# 05_MIMXRT1170_PART1.net
KiCad netlist of a schematic drawn in Altium Designer
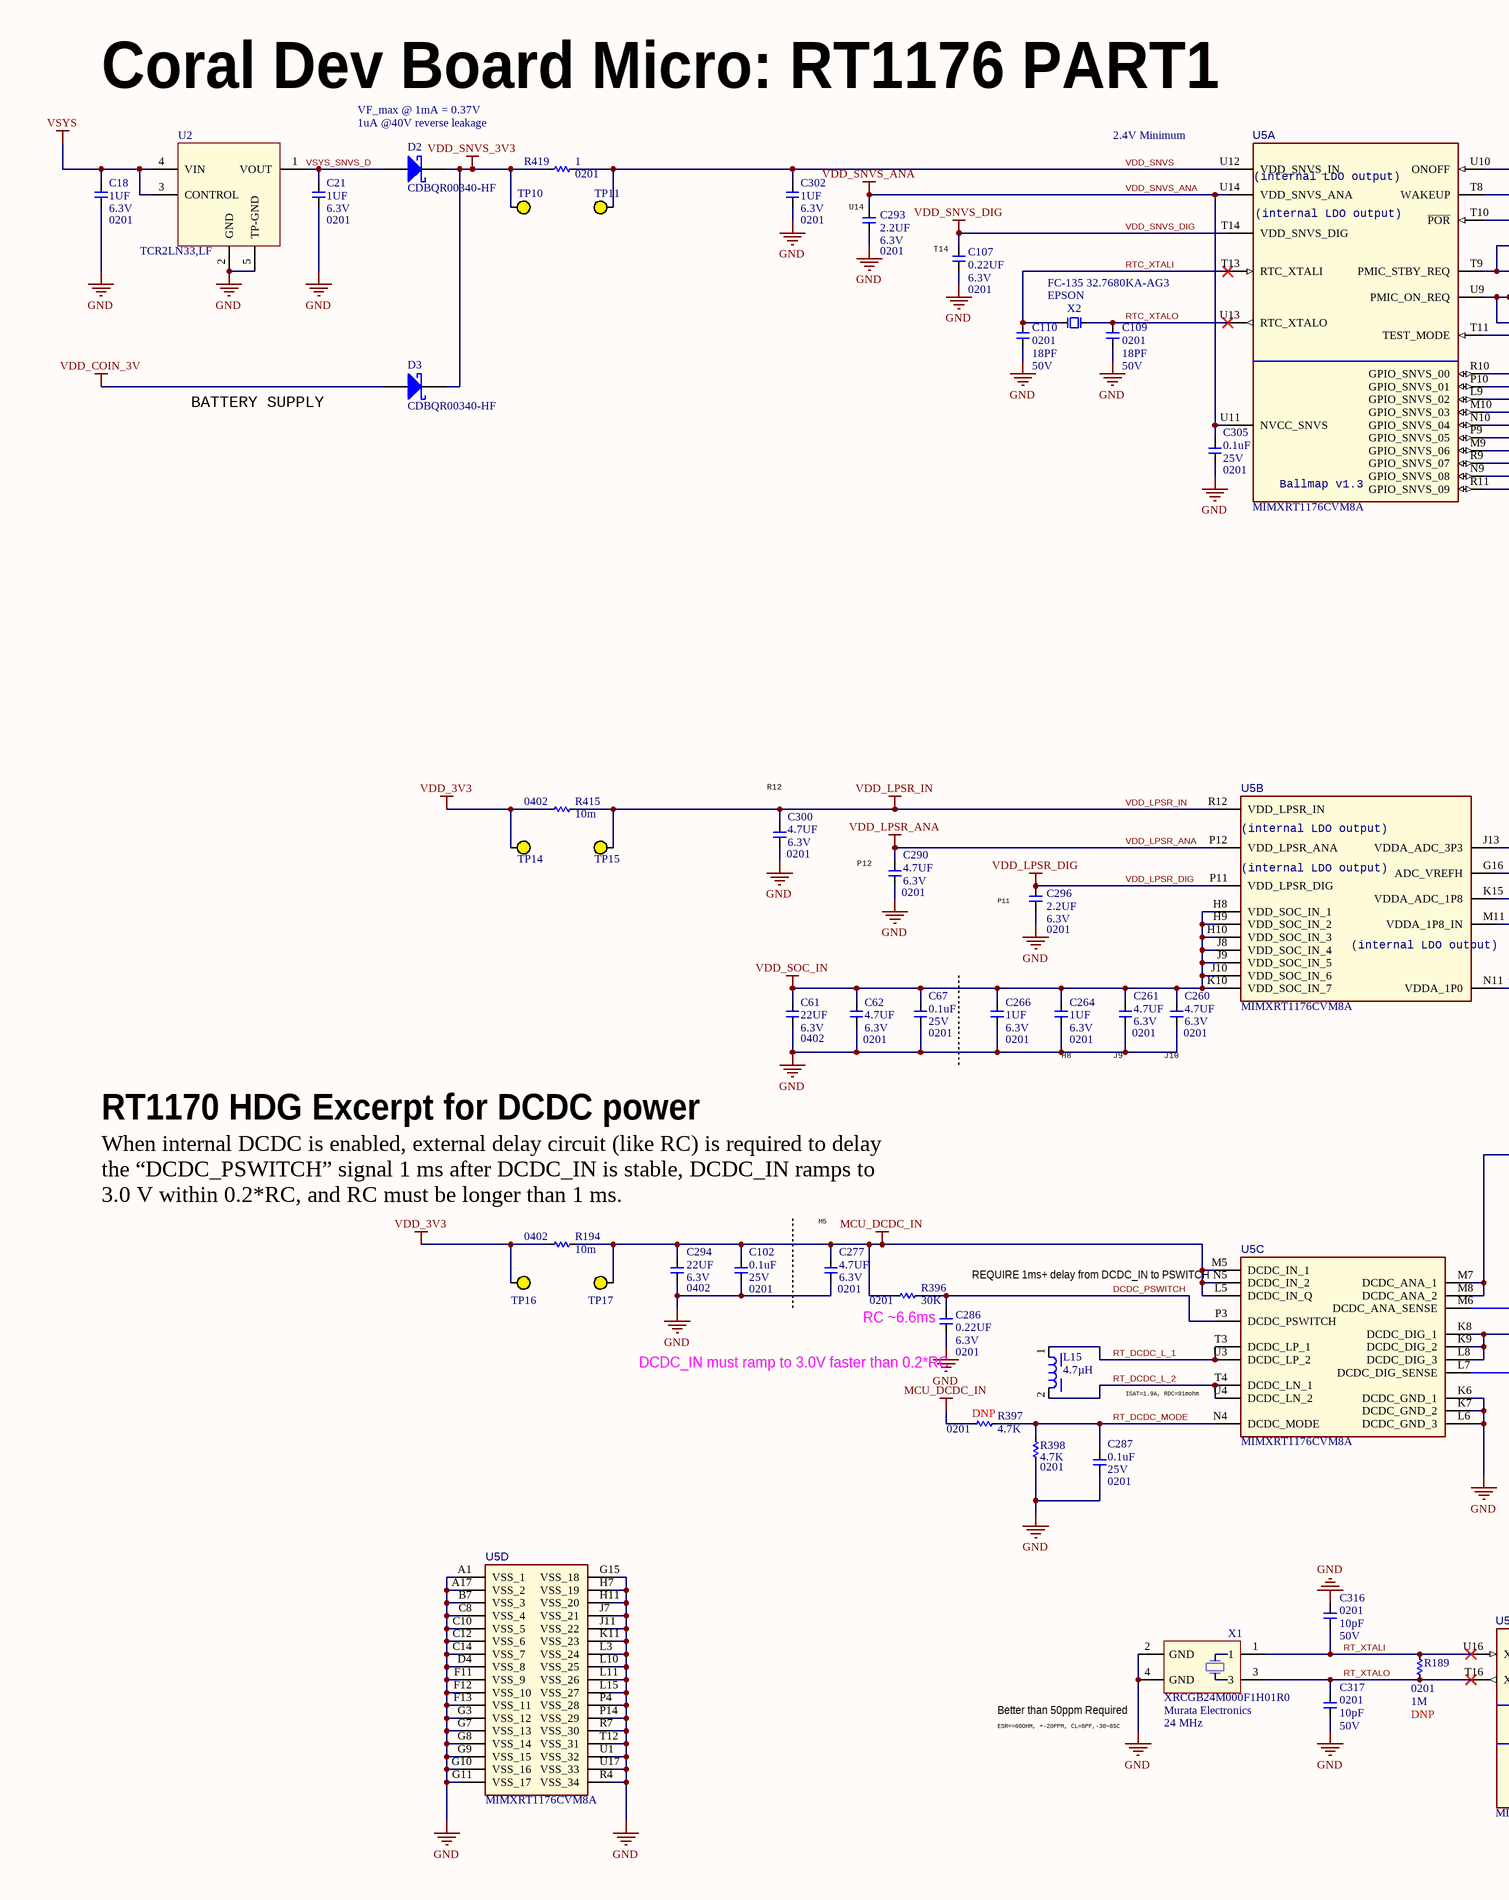
[diagram p0: 05 MIMXRT1170 PART1.SchDoc, left]
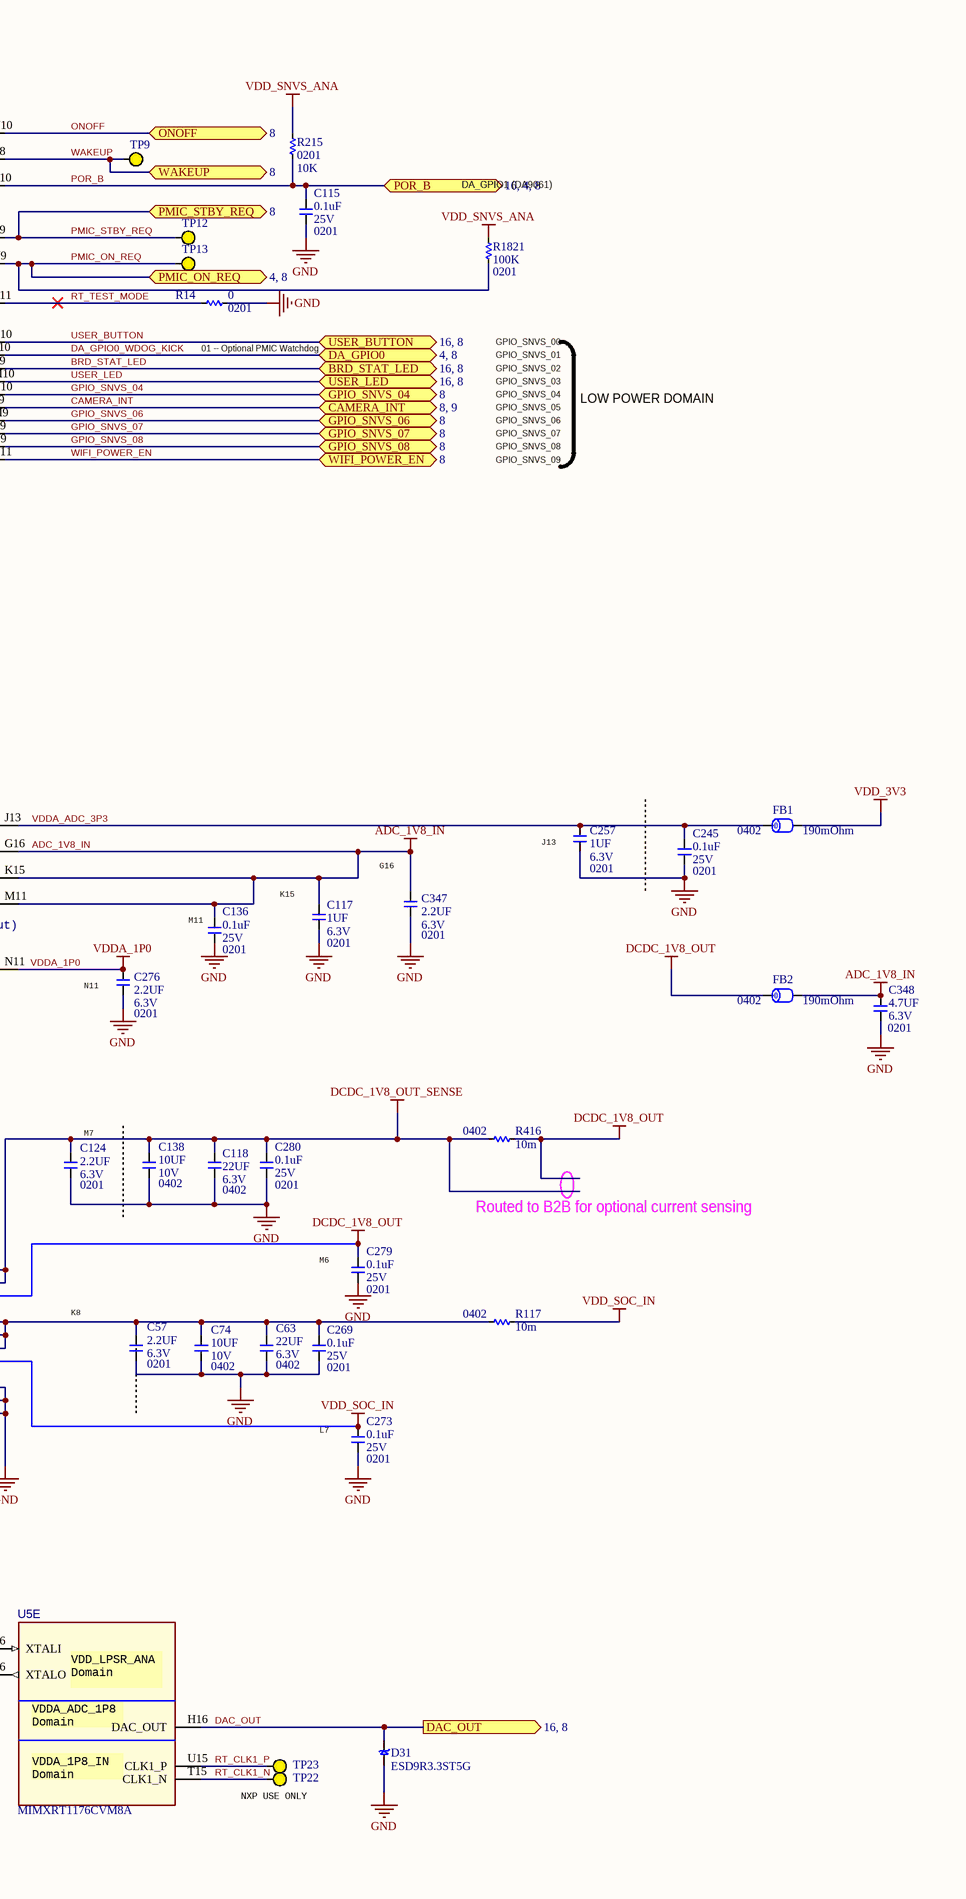
[diagram p1: 05 MIMXRT1170 PART1.SchDoc, right]

(export (version "E")
  (design (tool "Eeschema 10.0.6"))
  (components
    (comp (ref "C18")
      (value "1UF")
      (footprint "C0201_H0.39MM")
      (description "CAP, CER, X6S, 1uF, 20%, 6.3V, 0201, 0.39mm")
      (fields
        (field (name "MFG") "MURATA")
        (field (name "PACKAGE") "0201")
        (field (name "VOLTAGE") "6.3V")
        (field (name "TOLERANCE") "20%")
      )
      (libsource (lib "AltiumReleaseLibDB") (part "__Template_Cap"))
    )
    (comp (ref "C21")
      (value "1UF")
      (footprint "C0201_H0.39MM")
      (description "CAP, CER, X6S, 1uF, 20%, 6.3V, 0201, 0.39mm")
      (fields
        (field (name "MFG") "MURATA")
        (field (name "PACKAGE") "0201")
        (field (name "VOLTAGE") "6.3V")
        (field (name "TOLERANCE") "20%")
      )
      (libsource (lib "AltiumReleaseLibDB") (part "__Template_Cap"))
    )
    (comp (ref "C57")
      (value "2.2UF")
      (footprint "C0201_H0.39MM")
      (description "CAP, CER, X5R, 2.2uF, 20%, 6.3V, 0201, 0.39mm")
      (fields
        (field (name "MFG") "YAGEO")
        (field (name "PACKAGE") "0201")
        (field (name "VOLTAGE") "6.3V")
        (field (name "TOLERANCE") "20%")
      )
      (libsource (lib "AltiumReleaseLibDB") (part "__Template_Cap"))
    )
    (comp (ref "C61")
      (value "22UF")
      (footprint "C0402")
      (description "CAP, CER, X5R, 22uF, 20%, 6.3V, 0402")
      (fields
        (field (name "MFG") "AVX")
        (field (name "PACKAGE") "0402")
        (field (name "VOLTAGE") "6.3V")
        (field (name "TOLERANCE") "20%")
      )
      (libsource (lib "AltiumReleaseLibDB") (part "__Template_Cap"))
    )
    (comp (ref "C62")
      (value "4.7UF")
      (footprint "C0201Y")
      (description "CAP, CER, X5R, 4.7uF, 20%, 6.3V, 0201")
      (fields
        (field (name "MFG") "MURATA")
        (field (name "PACKAGE") "0201")
        (field (name "VOLTAGE") "6.3V")
        (field (name "TOLERANCE") "20%")
      )
      (libsource (lib "AltiumReleaseLibDB") (part "__Template_Cap"))
    )
    (comp (ref "C63")
      (value "22UF")
      (footprint "C0402")
      (description "CAP, CER, X5R, 22uF, 20%, 6.3V, 0402")
      (fields
        (field (name "MFG") "AVX")
        (field (name "PACKAGE") "0402")
        (field (name "VOLTAGE") "6.3V")
        (field (name "TOLERANCE") "20%")
      )
      (libsource (lib "AltiumReleaseLibDB") (part "__Template_Cap"))
    )
    (comp (ref "C67")
      (value "0.1uF")
      (footprint "C0201Y")
      (description "CAP, CER, X5R, 0.1uF, 25V, 20%, 0201, 0.33mm T")
      (fields
        (field (name "MFG") "MURATA")
        (field (name "PACKAGE") "0201")
        (field (name "VOLTAGE") "25V")
        (field (name "TOLERANCE") "20%")
      )
      (libsource (lib "AltiumReleaseLibDB") (part "__Template_Cap"))
    )
    (comp (ref "C74")
      (value "10UF")
      (footprint "C0402")
      (description "CAP, CER, X5R, 10uF, 10V, 20%, 0402, 0.7mm T")
      (fields
        (field (name "MFG") "SAMSUNG")
        (field (name "PACKAGE") "0402")
        (field (name "VOLTAGE") "10V")
        (field (name "TOLERANCE") "20%")
      )
      (libsource (lib "AltiumReleaseLibDB") (part "__Template_Cap"))
    )
    (comp (ref "C102")
      (value "0.1uF")
      (footprint "C0201Y")
      (description "CAP, CER, X5R, 0.1uF, 25V, 20%, 0201, 0.33mm T")
      (fields
        (field (name "MFG") "MURATA")
        (field (name "PACKAGE") "0201")
        (field (name "VOLTAGE") "25V")
        (field (name "TOLERANCE") "20%")
      )
      (libsource (lib "AltiumReleaseLibDB") (part "__Template_Cap"))
    )
    (comp (ref "C107")
      (value "0.22UF")
      (footprint "C0201")
      (description "CAP, CER, X5R, 0.22uF, 6.3V, 10%, 0201, 0.33mm T")
      (fields
        (field (name "MFG") "TDK")
        (field (name "PACKAGE") "0201")
        (field (name "VOLTAGE") "6.3V")
        (field (name "TOLERANCE") "10%")
      )
      (libsource (lib "AltiumReleaseLibDB") (part "__Template_Cap"))
    )
    (comp (ref "C109")
      (value "18PF")
      (footprint "C0201Y")
      (description "CAP, CER, C0G, 18pF, 50V, 2%, 0201, 0.33mm T")
      (fields
        (field (name "MFG") "MURATA")
        (field (name "PACKAGE") "0201")
        (field (name "VOLTAGE") "50V")
        (field (name "TOLERANCE") "2%")
      )
      (libsource (lib "AltiumReleaseLibDB") (part "__Template_Cap"))
    )
    (comp (ref "C110")
      (value "18PF")
      (footprint "C0201Y")
      (description "CAP, CER, C0G, 18pF, 50V, 2%, 0201, 0.33mm T")
      (fields
        (field (name "MFG") "MURATA")
        (field (name "PACKAGE") "0201")
        (field (name "VOLTAGE") "50V")
        (field (name "TOLERANCE") "2%")
      )
      (libsource (lib "AltiumReleaseLibDB") (part "__Template_Cap"))
    )
    (comp (ref "C115")
      (value "0.1uF")
      (footprint "C0201Y")
      (description "CAP, CER, X5R, 0.1uF, 25V, 20%, 0201, 0.33mm T")
      (fields
        (field (name "MFG") "MURATA")
        (field (name "PACKAGE") "0201")
        (field (name "VOLTAGE") "25V")
        (field (name "TOLERANCE") "20%")
      )
      (libsource (lib "AltiumReleaseLibDB") (part "__Template_Cap"))
    )
    (comp (ref "C117")
      (value "1UF")
      (footprint "C0201_H0.39MM")
      (description "CAP, CER, X6S, 1uF, 20%, 6.3V, 0201, 0.39mm")
      (fields
        (field (name "MFG") "MURATA")
        (field (name "PACKAGE") "0201")
        (field (name "VOLTAGE") "6.3V")
        (field (name "TOLERANCE") "20%")
      )
      (libsource (lib "AltiumReleaseLibDB") (part "__Template_Cap"))
    )
    (comp (ref "C118")
      (value "22UF")
      (footprint "C0402")
      (description "CAP, CER, X5R, 22uF, 20%, 6.3V, 0402")
      (fields
        (field (name "MFG") "AVX")
        (field (name "PACKAGE") "0402")
        (field (name "VOLTAGE") "6.3V")
        (field (name "TOLERANCE") "20%")
      )
      (libsource (lib "AltiumReleaseLibDB") (part "__Template_Cap"))
    )
    (comp (ref "C124")
      (value "2.2UF")
      (footprint "C0201_H0.39MM")
      (description "CAP, CER, X5R, 2.2uF, 20%, 6.3V, 0201, 0.39mm")
      (fields
        (field (name "MFG") "YAGEO")
        (field (name "PACKAGE") "0201")
        (field (name "VOLTAGE") "6.3V")
        (field (name "TOLERANCE") "20%")
      )
      (libsource (lib "AltiumReleaseLibDB") (part "__Template_Cap"))
    )
    (comp (ref "C136")
      (value "0.1uF")
      (footprint "C0201Y")
      (description "CAP, CER, X5R, 0.1uF, 25V, 20%, 0201, 0.33mm T")
      (fields
        (field (name "MFG") "MURATA")
        (field (name "PACKAGE") "0201")
        (field (name "VOLTAGE") "25V")
        (field (name "TOLERANCE") "20%")
      )
      (libsource (lib "AltiumReleaseLibDB") (part "__Template_Cap"))
    )
    (comp (ref "C138")
      (value "10UF")
      (footprint "C0402")
      (description "CAP, CER, X5R, 10uF, 10V, 20%, 0402, 0.7mm T")
      (fields
        (field (name "MFG") "SAMSUNG")
        (field (name "PACKAGE") "0402")
        (field (name "VOLTAGE") "10V")
        (field (name "TOLERANCE") "20%")
      )
      (libsource (lib "AltiumReleaseLibDB") (part "__Template_Cap"))
    )
    (comp (ref "C245")
      (value "0.1uF")
      (footprint "C0201Y")
      (description "CAP, CER, X5R, 0.1uF, 25V, 20%, 0201, 0.33mm T")
      (fields
        (field (name "MFG") "MURATA")
        (field (name "PACKAGE") "0201")
        (field (name "VOLTAGE") "25V")
        (field (name "TOLERANCE") "20%")
      )
      (libsource (lib "AltiumReleaseLibDB") (part "__Template_Cap"))
    )
    (comp (ref "C257")
      (value "1UF")
      (footprint "C0201_H0.39MM")
      (description "CAP, CER, X6S, 1uF, 20%, 6.3V, 0201, 0.39mm")
      (fields
        (field (name "MFG") "MURATA")
        (field (name "PACKAGE") "0201")
        (field (name "VOLTAGE") "6.3V")
        (field (name "TOLERANCE") "20%")
      )
      (libsource (lib "AltiumReleaseLibDB") (part "__Template_Cap"))
    )
    (comp (ref "C260")
      (value "4.7UF")
      (footprint "C0201Y")
      (description "CAP, CER, X5R, 4.7uF, 20%, 6.3V, 0201")
      (fields
        (field (name "MFG") "MURATA")
        (field (name "PACKAGE") "0201")
        (field (name "VOLTAGE") "6.3V")
        (field (name "TOLERANCE") "20%")
      )
      (libsource (lib "AltiumReleaseLibDB") (part "__Template_Cap"))
    )
    (comp (ref "C261")
      (value "4.7UF")
      (footprint "C0201Y")
      (description "CAP, CER, X5R, 4.7uF, 20%, 6.3V, 0201")
      (fields
        (field (name "MFG") "MURATA")
        (field (name "PACKAGE") "0201")
        (field (name "VOLTAGE") "6.3V")
        (field (name "TOLERANCE") "20%")
      )
      (libsource (lib "AltiumReleaseLibDB") (part "__Template_Cap"))
    )
    (comp (ref "C264")
      (value "1UF")
      (footprint "C0201_H0.39MM")
      (description "CAP, CER, X6S, 1uF, 20%, 6.3V, 0201, 0.39mm")
      (fields
        (field (name "MFG") "MURATA")
        (field (name "PACKAGE") "0201")
        (field (name "VOLTAGE") "6.3V")
        (field (name "TOLERANCE") "20%")
      )
      (libsource (lib "AltiumReleaseLibDB") (part "__Template_Cap"))
    )
    (comp (ref "C266")
      (value "1UF")
      (footprint "C0201_H0.39MM")
      (description "CAP, CER, X6S, 1uF, 20%, 6.3V, 0201, 0.39mm")
      (fields
        (field (name "MFG") "MURATA")
        (field (name "PACKAGE") "0201")
        (field (name "VOLTAGE") "6.3V")
        (field (name "TOLERANCE") "20%")
      )
      (libsource (lib "AltiumReleaseLibDB") (part "__Template_Cap"))
    )
    (comp (ref "C269")
      (value "0.1uF")
      (footprint "C0201Y")
      (description "CAP, CER, X5R, 0.1uF, 25V, 20%, 0201, 0.33mm T")
      (fields
        (field (name "MFG") "MURATA")
        (field (name "PACKAGE") "0201")
        (field (name "VOLTAGE") "25V")
        (field (name "TOLERANCE") "20%")
      )
      (libsource (lib "AltiumReleaseLibDB") (part "__Template_Cap"))
    )
    (comp (ref "C273")
      (value "0.1uF")
      (footprint "C0201Y")
      (description "CAP, CER, X5R, 0.1uF, 25V, 20%, 0201, 0.33mm T")
      (fields
        (field (name "MFG") "MURATA")
        (field (name "PACKAGE") "0201")
        (field (name "VOLTAGE") "25V")
        (field (name "TOLERANCE") "20%")
      )
      (libsource (lib "AltiumReleaseLibDB") (part "__Template_Cap"))
    )
    (comp (ref "C276")
      (value "2.2UF")
      (footprint "C0201_H0.39MM")
      (description "CAP, CER, X5R, 2.2uF, 20%, 6.3V, 0201, 0.39mm")
      (fields
        (field (name "MFG") "YAGEO")
        (field (name "PACKAGE") "0201")
        (field (name "VOLTAGE") "6.3V")
        (field (name "TOLERANCE") "20%")
      )
      (libsource (lib "AltiumReleaseLibDB") (part "__Template_Cap"))
    )
    (comp (ref "C277")
      (value "4.7UF")
      (footprint "C0201Y")
      (description "CAP, CER, X5R, 4.7uF, 20%, 6.3V, 0201")
      (fields
        (field (name "MFG") "MURATA")
        (field (name "PACKAGE") "0201")
        (field (name "VOLTAGE") "6.3V")
        (field (name "TOLERANCE") "20%")
      )
      (libsource (lib "AltiumReleaseLibDB") (part "__Template_Cap"))
    )
    (comp (ref "C279")
      (value "0.1uF")
      (footprint "C0201Y")
      (description "CAP, CER, X5R, 0.1uF, 25V, 20%, 0201, 0.33mm T")
      (fields
        (field (name "MFG") "MURATA")
        (field (name "PACKAGE") "0201")
        (field (name "VOLTAGE") "25V")
        (field (name "TOLERANCE") "20%")
      )
      (libsource (lib "AltiumReleaseLibDB") (part "__Template_Cap"))
    )
    (comp (ref "C280")
      (value "0.1uF")
      (footprint "C0201Y")
      (description "CAP, CER, X5R, 0.1uF, 25V, 20%, 0201, 0.33mm T")
      (fields
        (field (name "MFG") "MURATA")
        (field (name "PACKAGE") "0201")
        (field (name "VOLTAGE") "25V")
        (field (name "TOLERANCE") "20%")
      )
      (libsource (lib "AltiumReleaseLibDB") (part "__Template_Cap"))
    )
    (comp (ref "C286")
      (value "0.22UF")
      (footprint "C0201")
      (description "CAP, CER, X5R, 0.22uF, 6.3V, 10%, 0201, 0.33mm T")
      (fields
        (field (name "MFG") "TDK")
        (field (name "PACKAGE") "0201")
        (field (name "VOLTAGE") "6.3V")
        (field (name "TOLERANCE") "10%")
      )
      (libsource (lib "AltiumReleaseLibDB") (part "__Template_Cap"))
    )
    (comp (ref "C287")
      (value "0.1uF")
      (footprint "C0201Y")
      (description "CAP, CER, X5R, 0.1uF, 25V, 20%, 0201, 0.33mm T")
      (fields
        (field (name "MFG") "MURATA")
        (field (name "PACKAGE") "0201")
        (field (name "VOLTAGE") "25V")
        (field (name "TOLERANCE") "20%")
      )
      (libsource (lib "AltiumReleaseLibDB") (part "__Template_Cap"))
    )
    (comp (ref "C290")
      (value "4.7UF")
      (footprint "C0201Y")
      (description "CAP, CER, X5R, 4.7uF, 20%, 6.3V, 0201")
      (fields
        (field (name "MFG") "MURATA")
        (field (name "PACKAGE") "0201")
        (field (name "VOLTAGE") "6.3V")
        (field (name "TOLERANCE") "20%")
      )
      (libsource (lib "AltiumReleaseLibDB") (part "__Template_Cap"))
    )
    (comp (ref "C293")
      (value "2.2UF")
      (footprint "C0201_H0.39MM")
      (description "CAP, CER, X5R, 2.2uF, 20%, 6.3V, 0201, 0.39mm")
      (fields
        (field (name "MFG") "YAGEO")
        (field (name "PACKAGE") "0201")
        (field (name "VOLTAGE") "6.3V")
        (field (name "TOLERANCE") "20%")
      )
      (libsource (lib "AltiumReleaseLibDB") (part "__Template_Cap"))
    )
    (comp (ref "C294")
      (value "22UF")
      (footprint "C0402")
      (description "CAP, CER, X5R, 22uF, 20%, 6.3V, 0402")
      (fields
        (field (name "MFG") "AVX")
        (field (name "PACKAGE") "0402")
        (field (name "VOLTAGE") "6.3V")
        (field (name "TOLERANCE") "20%")
      )
      (libsource (lib "AltiumReleaseLibDB") (part "__Template_Cap"))
    )
    (comp (ref "C296")
      (value "2.2UF")
      (footprint "C0201_H0.39MM")
      (description "CAP, CER, X5R, 2.2uF, 20%, 6.3V, 0201, 0.39mm")
      (fields
        (field (name "MFG") "YAGEO")
        (field (name "PACKAGE") "0201")
        (field (name "VOLTAGE") "6.3V")
        (field (name "TOLERANCE") "20%")
      )
      (libsource (lib "AltiumReleaseLibDB") (part "__Template_Cap"))
    )
    (comp (ref "C300")
      (value "4.7UF")
      (footprint "C0201Y")
      (description "CAP, CER, X5R, 4.7uF, 20%, 6.3V, 0201")
      (fields
        (field (name "MFG") "MURATA")
        (field (name "PACKAGE") "0201")
        (field (name "VOLTAGE") "6.3V")
        (field (name "TOLERANCE") "20%")
      )
      (libsource (lib "AltiumReleaseLibDB") (part "__Template_Cap"))
    )
    (comp (ref "C302")
      (value "1UF")
      (footprint "C0201_H0.39MM")
      (description "CAP, CER, X6S, 1uF, 20%, 6.3V, 0201, 0.39mm")
      (fields
        (field (name "MFG") "MURATA")
        (field (name "PACKAGE") "0201")
        (field (name "VOLTAGE") "6.3V")
        (field (name "TOLERANCE") "20%")
      )
      (libsource (lib "AltiumReleaseLibDB") (part "__Template_Cap"))
    )
    (comp (ref "C305")
      (value "0.1uF")
      (footprint "C0201Y")
      (description "CAP, CER, X5R, 0.1uF, 25V, 20%, 0201, 0.33mm T")
      (fields
        (field (name "MFG") "MURATA")
        (field (name "PACKAGE") "0201")
        (field (name "VOLTAGE") "25V")
        (field (name "TOLERANCE") "20%")
      )
      (libsource (lib "AltiumReleaseLibDB") (part "__Template_Cap"))
    )
    (comp (ref "C316")
      (value "10pF")
      (footprint "C0201Y")
      (description "CAP, CER, NP0, 10pf, 50V, 5%, 0201, 0.33mm T")
      (fields
        (field (name "MFG") "MURATA")
        (field (name "PACKAGE") "0201")
        (field (name "VOLTAGE") "50V")
        (field (name "TOLERANCE") "5%")
      )
      (libsource (lib "AltiumReleaseLibDB") (part "__Template_Cap"))
    )
    (comp (ref "C317")
      (value "10pF")
      (footprint "C0201Y")
      (description "CAP, CER, NP0, 10pf, 50V, 5%, 0201, 0.33mm T")
      (fields
        (field (name "MFG") "MURATA")
        (field (name "PACKAGE") "0201")
        (field (name "VOLTAGE") "50V")
        (field (name "TOLERANCE") "5%")
      )
      (libsource (lib "AltiumReleaseLibDB") (part "__Template_Cap"))
    )
    (comp (ref "C347")
      (value "2.2UF")
      (footprint "C0201_H0.39MM")
      (description "CAP, CER, X5R, 2.2uF, 20%, 6.3V, 0201, 0.39mm")
      (fields
        (field (name "MFG") "YAGEO")
        (field (name "PACKAGE") "0201")
        (field (name "VOLTAGE") "6.3V")
        (field (name "TOLERANCE") "20%")
      )
      (libsource (lib "AltiumReleaseLibDB") (part "__Template_Cap"))
    )
    (comp (ref "C348")
      (value "4.7UF")
      (footprint "C0201Y")
      (description "CAP, CER, X5R, 4.7uF, 20%, 6.3V, 0201")
      (fields
        (field (name "MFG") "MURATA")
        (field (name "PACKAGE") "0201")
        (field (name "VOLTAGE") "6.3V")
        (field (name "TOLERANCE") "20%")
      )
      (libsource (lib "AltiumReleaseLibDB") (part "__Template_Cap"))
    )
    (comp (ref "D2")
      (value "CDBQR00340-HF")
      (footprint "D0402_H0.55MM")
      (description "DIODE, SCHOTTKY, 40V VRRM, 30mA IO, 500mA SURGE, 0402")
      (fields (field (name "MFG") "Comchip Technology") (field (name "Comment") "__Template_DIODE_SCHOTTKY"))
      (libsource (lib "AltiumReleaseLibDB") (part "__Template_DIODE_SCHOTTKY"))
    )
    (comp (ref "D3")
      (value "CDBQR00340-HF")
      (footprint "D0402_H0.55MM")
      (description "DIODE, SCHOTTKY, 40V VRRM, 30mA IO, 500mA SURGE, 0402")
      (fields (field (name "MFG") "Comchip Technology") (field (name "Comment") "__Template_DIODE_SCHOTTKY"))
      (libsource (lib "AltiumReleaseLibDB") (part "__Template_DIODE_SCHOTTKY"))
    )
    (comp (ref "D31")
      (value "ESD9R3.3ST5G")
      (footprint "SOD1060X40")
      (description "TVS, DIODE, UNIDIR, 3.3VRWM, 4.8VBR, 7.8VCL, SOD-923")
      (fields (field (name "MFG") "ON Semiconductor") (field (name "Comment") "__Template_Diode_TVS_A/K"))
      (libsource (lib "AltiumReleaseLibDB") (part "__Template_Diode_TVS_A/K"))
    )
    (comp (ref "FB1")
      (value "__Template_Ferrite_Bead")
      (footprint "L0402_H0.55MM")
      (description "FERRITE, BEAD, 120 OHMS@100MHZ, 25%, 550mA, 190 mOHM DCR, 0402")
      (fields
        (field (name "MFG") "Murata Electronics")
        (field (name "PACKAGE") "0402")
        (field (name "RDC MAX") "190mOhm")
      )
      (libsource (lib "AltiumReleaseLibDB") (part "__Template_Ferrite_Bead"))
    )
    (comp (ref "FB2")
      (value "__Template_Ferrite_Bead")
      (footprint "L0402_H0.55MM")
      (description "FERRITE, BEAD, 120 OHMS@100MHZ, 25%, 550mA, 190 mOHM DCR, 0402")
      (fields
        (field (name "MFG") "Murata Electronics")
        (field (name "PACKAGE") "0402")
        (field (name "RDC MAX") "190mOhm")
      )
      (libsource (lib "AltiumReleaseLibDB") (part "__Template_Ferrite_Bead"))
    )
    (comp (ref "L15")
      (value "4.7µH")
      (footprint "IND_74404041047")
      (description "IND, WIREWOUND, SEMI-SHIELDED, 4.7uH, 1.55A, 20%, DCR 0.091, SMD")
      (fields (field (name "MFG") "Würth Elektronik") (field (name "TOLERANCE") "20%"))
      (libsource (lib "AltiumReleaseLibDB") (part "IND_74404041047"))
    )
    (comp (ref "R14")
      (value "0")
      (footprint "R0201")
      (description "RES, 0.0, 1/20W, 0201")
      (fields (field (name "MFG") "PANASONIC") (field (name "PACKAGE") "0201") (field (name "POWER") "1/20W"))
      (libsource (lib "AltiumReleaseLibDB") (part "__Template_Resistor"))
    )
    (comp (ref "R117")
      (value "10m")
      (footprint "R0402")
      (description "RES, 0.01, 5%, 1/4W, 0402")
      (fields (field (name "MFG") "YAGEO") (field (name "PACKAGE") "0402") (field (name "POWER") "1/4W"))
      (libsource (lib "AltiumReleaseLibDB") (part "__Template_Resistor"))
    )
    (comp (ref "R189")
      (value "1M")
      (footprint "R0201")
      (description "RES, 1M, 1%, 1/20W, 0201")
      (fields
        (field (name "MFG") "PANASONIC")
        (field (name "PACKAGE") "0201")
        (field (name "POWER") "1/20W")
        (field (name "DNP") "DNP")
      )
      (libsource (lib "AltiumReleaseLibDB") (part "__Template_Resistor"))
    )
    (comp (ref "R194")
      (value "10m")
      (footprint "R0402")
      (description "RES, 0.01, 5%, 1/4W, 0402")
      (fields (field (name "MFG") "YAGEO") (field (name "PACKAGE") "0402") (field (name "POWER") "1/4W"))
      (libsource (lib "AltiumReleaseLibDB") (part "__Template_Resistor"))
    )
    (comp (ref "R215")
      (value "10K")
      (footprint "R0201")
      (description "RES, 10K, 1%, 1/20W, 0201")
      (fields (field (name "MFG") "YAGEO") (field (name "PACKAGE") "0201") (field (name "POWER") "1/20W"))
      (libsource (lib "AltiumReleaseLibDB") (part "__Template_Resistor"))
    )
    (comp (ref "R396")
      (value "30K")
      (footprint "R0201")
      (description "RES, 30K, 5%, 1/20W, 0201")
      (fields (field (name "MFG") "PANASONIC") (field (name "PACKAGE") "0201") (field (name "POWER") "1/20W"))
      (libsource (lib "AltiumReleaseLibDB") (part "__Template_Resistor"))
    )
    (comp (ref "R397")
      (value "4.7K")
      (footprint "R0201")
      (description "RES, 4.7K, 5%, 1/20W, 0201")
      (fields
        (field (name "MFG") "YAGEO")
        (field (name "PACKAGE") "0201")
        (field (name "POWER") "1/20W")
        (field (name "DNP") "DNP")
      )
      (libsource (lib "AltiumReleaseLibDB") (part "__Template_Resistor"))
    )
    (comp (ref "R398")
      (value "4.7K")
      (footprint "R0201")
      (description "RES, 4.7K, 5%, 1/20W, 0201")
      (fields (field (name "MFG") "YAGEO") (field (name "PACKAGE") "0201") (field (name "POWER") "1/20W"))
      (libsource (lib "AltiumReleaseLibDB") (part "__Template_Resistor"))
    )
    (comp (ref "R415")
      (value "10m")
      (footprint "R0402")
      (description "RES, 0.01, 5%, 1/4W, 0402")
      (fields (field (name "MFG") "YAGEO") (field (name "PACKAGE") "0402") (field (name "POWER") "1/4W"))
      (libsource (lib "AltiumReleaseLibDB") (part "__Template_Resistor"))
    )
    (comp (ref "R416")
      (value "10m")
      (footprint "R0402")
      (description "RES, 0.01, 5%, 1/4W, 0402")
      (fields (field (name "MFG") "YAGEO") (field (name "PACKAGE") "0402") (field (name "POWER") "1/4W"))
      (libsource (lib "AltiumReleaseLibDB") (part "__Template_Resistor"))
    )
    (comp (ref "R419")
      (value "1")
      (footprint "R0201")
      (description "RES, 1.0, 1%, 1/20W, 0201")
      (fields
        (field (name "MFG") "STACKPOLE ELECTRONICS")
        (field (name "PACKAGE") "0201")
        (field (name "POWER") "1/20W")
      )
      (libsource (lib "AltiumReleaseLibDB") (part "__Template_Resistor"))
    )
    (comp (ref "R1821")
      (value "100K")
      (footprint "R0201")
      (description "RES, 100K, 1%, 1/20W, 0201")
      (fields (field (name "MFG") "PANASONIC") (field (name "PACKAGE") "0201") (field (name "POWER") "1/20W"))
      (libsource (lib "AltiumReleaseLibDB") (part "__Template_Resistor"))
    )
    (comp (ref "TP9")
      (value "TESTPAD_30MIL")
      (footprint "TESTPAD_SMT_30MIL")
      (description "TESTPAD_SMT_30MIL")
      (fields (field (name "MFG") "_PCB Feature"))
      (libsource (lib "AltiumReleaseLibDB") (part "TESTPAD_30MIL"))
    )
    (comp (ref "TP10")
      (value "TESTPAD_30MIL")
      (footprint "TESTPAD_SMT_30MIL")
      (description "TESTPAD_SMT_30MIL")
      (fields (field (name "MFG") "_PCB Feature"))
      (libsource (lib "AltiumReleaseLibDB") (part "TESTPAD_30MIL"))
    )
    (comp (ref "TP11")
      (value "TESTPAD_30MIL")
      (footprint "TESTPAD_SMT_30MIL")
      (description "TESTPAD_SMT_30MIL")
      (fields (field (name "MFG") "_PCB Feature"))
      (libsource (lib "AltiumReleaseLibDB") (part "TESTPAD_30MIL"))
    )
    (comp (ref "TP12")
      (value "TESTPAD_30MIL")
      (footprint "TESTPAD_SMT_30MIL")
      (description "TESTPAD_SMT_30MIL")
      (fields (field (name "MFG") "_PCB Feature"))
      (libsource (lib "AltiumReleaseLibDB") (part "TESTPAD_30MIL"))
    )
    (comp (ref "TP13")
      (value "TESTPAD_30MIL")
      (footprint "TESTPAD_SMT_30MIL")
      (description "TESTPAD_SMT_30MIL")
      (fields (field (name "MFG") "_PCB Feature"))
      (libsource (lib "AltiumReleaseLibDB") (part "TESTPAD_30MIL"))
    )
    (comp (ref "TP14")
      (value "TESTPAD_30MIL")
      (footprint "TESTPAD_SMT_30MIL")
      (description "TESTPAD_SMT_30MIL")
      (fields (field (name "MFG") "_PCB Feature"))
      (libsource (lib "AltiumReleaseLibDB") (part "TESTPAD_30MIL"))
    )
    (comp (ref "TP15")
      (value "TESTPAD_30MIL")
      (footprint "TESTPAD_SMT_30MIL")
      (description "TESTPAD_SMT_30MIL")
      (fields (field (name "MFG") "_PCB Feature"))
      (libsource (lib "AltiumReleaseLibDB") (part "TESTPAD_30MIL"))
    )
    (comp (ref "TP16")
      (value "TESTPAD_30MIL")
      (footprint "TESTPAD_SMT_30MIL")
      (description "TESTPAD_SMT_30MIL")
      (fields (field (name "MFG") "_PCB Feature"))
      (libsource (lib "AltiumReleaseLibDB") (part "TESTPAD_30MIL"))
    )
    (comp (ref "TP17")
      (value "TESTPAD_30MIL")
      (footprint "TESTPAD_SMT_30MIL")
      (description "TESTPAD_SMT_30MIL")
      (fields (field (name "MFG") "_PCB Feature"))
      (libsource (lib "AltiumReleaseLibDB") (part "TESTPAD_30MIL"))
    )
    (comp (ref "TP22")
      (value "TESTPAD_30MIL")
      (footprint "TESTPAD_SMT_30MIL")
      (description "TESTPAD_SMT_30MIL")
      (fields (field (name "MFG") "_PCB Feature"))
      (libsource (lib "AltiumReleaseLibDB") (part "TESTPAD_30MIL"))
    )
    (comp (ref "TP23")
      (value "TESTPAD_30MIL")
      (footprint "TESTPAD_SMT_30MIL")
      (description "TESTPAD_SMT_30MIL")
      (fields (field (name "MFG") "_PCB Feature"))
      (libsource (lib "AltiumReleaseLibDB") (part "TESTPAD_30MIL"))
    )
    (comp (ref "U2")
      (value "REG_LIN_TCR2LN33")
      (footprint "SDFN80X80X40-5")
      (description "IC, REG, TCR2LN33, LINEAR, LDO, 5.5V VIN, 3.3V VOUT, CMOS O/P, SDFN-4")
      (fields (field (name "MFG") "Toshiba Semiconductor and Storage") (field (name "MFG P/N") "TCR2LN33,LF"))
      (libsource (lib "AltiumReleaseLibDB") (part "REG_LIN_TCR2LN33"))
    )
    (comp (ref "U5")
      (value "MCU_MIMXRT1176CVM8A")
      (footprint "BGA289C80P17X17_1400X14000X152")
      (description "IC, PROCESSOR, MIMXRT1176CV, ARM CORTEX-M4/M7, 2MB RAM, SDRAM, WLAN, BGA-289")
      (fields (field (name "MFG") "NXP Semiconductors") (field (name "MFG P/N") "MIMXRT1176CVM8A"))
      (libsource (lib "AltiumReleaseLibDB") (part "MCU_MIMXRT1176CVM8A"))
    )
    (comp (ref "X1")
      (value "XTAL_MURATA_XRCGB24M000F1H01R0")
      (footprint "XTAL_MURATA_XRCGB24M000F1H01R0")
      (description "XTAL, 24MHz, +/-10PPM STAB, +/-10PPM, 8pF, 80 OHM, SMD-4")
      (fields
        (field (name "MFG") "XRCGB24M000F1H01R0")
        (field (name "MFG P/N") "Murata Electronics")
        (field (name "FREQUENCY") "24 MHz")
      )
      (libsource (lib "AltiumReleaseLibDB") (part "XTAL_MURATA_XRCGB24M000F1H01R0"))
    )
    (comp (ref "X2")
      (value "__template_xtal")
      (footprint "XTAL_EPSON_ADUCM355BCCZ")
      (description "XTAL, 32.7680KHz, +/-20PPM, 7pF, 70 KOHM, SMD-2\nXTAL, 32.7680KHz, +/-20PPM, 7pF, 70 KOHM, SMD-2\"")
      (fields (field (name "MFG") "FC-135 32.7680KA-AG3") (field (name "MFG P/N") "EPSON"))
      (libsource (lib "AltiumReleaseLibDB") (part "__template_xtal"))
    )
  )
  (nets
    (net (code "1") (name "/BRD_STAT_LED") (class "Default")
      (node (ref "U5") (pin "L9") (pinfunction "GPIO_SNVS_02_L9") (pintype "bidirectional"))
    )
    (net (code "2") (name "/CAMERA_INT") (class "Default")
      (node (ref "U5") (pin "P9") (pinfunction "GPIO_SNVS_05_P9") (pintype "bidirectional"))
    )
    (net (code "3") (name "/DAC_OUT") (class "Default")
      (node (ref "D31") (pin "K") (pinfunction "K_K") (pintype "passive"))
      (node (ref "U5") (pin "H16") (pinfunction "DAC_OUT_H16") (pintype "passive"))
    )
    (net (code "4") (name "/DA_GPIO0_WDOG_KICK") (class "Default")
      (node (ref "U5") (pin "P10") (pinfunction "GPIO_SNVS_01_P10") (pintype "bidirectional"))
    )
    (net (code "5") (name "/DCDC_PSWITCH") (class "Default")
      (node (ref "C286") (pin "1") (pintype "passive"))
      (node (ref "R396") (pin "2") (pintype "passive"))
      (node (ref "U5") (pin "P3") (pinfunction "DCDC_PSWITCH_P3") (pintype "passive"))
    )
    (net (code "6") (name "/GPIO_SNVS_04") (class "Default")
      (node (ref "U5") (pin "N10") (pinfunction "GPIO_SNVS_04_N10") (pintype "bidirectional"))
    )
    (net (code "7") (name "/GPIO_SNVS_06") (class "Default")
      (node (ref "U5") (pin "M9") (pinfunction "GPIO_SNVS_06_M9") (pintype "bidirectional"))
    )
    (net (code "8") (name "/GPIO_SNVS_07") (class "Default")
      (node (ref "U5") (pin "R9") (pinfunction "GPIO_SNVS_07_R9") (pintype "bidirectional"))
    )
    (net (code "9") (name "/GPIO_SNVS_08") (class "Default")
      (node (ref "U5") (pin "N9") (pinfunction "GPIO_SNVS_08_N9") (pintype "bidirectional"))
    )
    (net (code "10") (name "/ONOFF") (class "Default")
      (node (ref "U5") (pin "U10") (pinfunction "ONOFF_U10") (pintype "input"))
    )
    (net (code "11") (name "/PMIC_ON_REQ") (class "Default")
      (node (ref "R1821") (pin "1") (pintype "passive"))
      (node (ref "TP13") (pin "1") (pintype "passive"))
      (node (ref "U5") (pin "U9") (pinfunction "PMIC_ON_REQ_U9") (pintype "passive"))
    )
    (net (code "12") (name "/PMIC_STBY_REQ") (class "Default")
      (node (ref "TP12") (pin "1") (pintype "passive"))
      (node (ref "U5") (pin "T9") (pinfunction "PMIC_STBY_REQ_T9") (pintype "passive"))
    )
    (net (code "13") (name "/POR_B") (class "Default")
      (node (ref "C115") (pin "1") (pintype "passive"))
      (node (ref "R215") (pin "1") (pintype "passive"))
      (node (ref "U5") (pin "T10") (pinfunction "~{POR}_T10") (pintype "input"))
    )
    (net (code "14") (name "/RTC_XTALI") (class "Default")
      (node (ref "C110") (pin "1") (pintype "passive"))
      (node (ref "U5") (pin "T13") (pinfunction "RTC_XTALI_T13") (pintype "input"))
      (node (ref "X2") (pin "1") (pinfunction "1_1") (pintype "passive"))
    )
    (net (code "15") (name "/RTC_XTALO") (class "Default")
      (node (ref "C109") (pin "1") (pintype "passive"))
      (node (ref "U5") (pin "U13") (pinfunction "RTC_XTALO_U13") (pintype "output"))
      (node (ref "X2") (pin "2") (pinfunction "2_2") (pintype "passive"))
    )
    (net (code "16") (name "/RT_CLK1_N") (class "Default")
      (node (ref "TP22") (pin "1") (pintype "passive"))
      (node (ref "U5") (pin "T15") (pinfunction "CLK1_N_T15") (pintype "passive"))
    )
    (net (code "17") (name "/RT_CLK1_P") (class "Default")
      (node (ref "TP23") (pin "1") (pintype "passive"))
      (node (ref "U5") (pin "U15") (pinfunction "CLK1_P_U15") (pintype "passive"))
    )
    (net (code "18") (name "/RT_DCDC_L_1") (class "Default")
      (node (ref "L15") (pin "1") (pintype "passive"))
      (node (ref "U5") (pin "T3") (pinfunction "DCDC_LP_1_T3") (pintype "passive"))
      (node (ref "U5") (pin "U3") (pinfunction "DCDC_LP_2_U3") (pintype "passive"))
    )
    (net (code "19") (name "/RT_DCDC_L_2") (class "Default")
      (node (ref "L15") (pin "2") (pintype "passive"))
      (node (ref "U5") (pin "T4") (pinfunction "DCDC_LN_1_T4") (pintype "passive"))
      (node (ref "U5") (pin "U4") (pinfunction "DCDC_LN_2_U4") (pintype "passive"))
    )
    (net (code "20") (name "/RT_DCDC_MODE") (class "Default")
      (node (ref "C287") (pin "1") (pintype "passive"))
      (node (ref "R397") (pin "2") (pintype "passive"))
      (node (ref "R398") (pin "2") (pintype "passive"))
      (node (ref "U5") (pin "N4") (pinfunction "DCDC_MODE_N4") (pintype "passive"))
    )
    (net (code "21") (name "/RT_TEST_MODE") (class "Default")
      (node (ref "R14") (pin "1") (pintype "passive"))
      (node (ref "U5") (pin "T11") (pinfunction "TEST_MODE_T11") (pintype "input"))
    )
    (net (code "22") (name "/RT_XTALI") (class "Default")
      (node (ref "C316") (pin "2") (pintype "passive"))
      (node (ref "R189") (pin "2") (pintype "passive"))
      (node (ref "U5") (pin "U16") (pinfunction "XTALI_U16") (pintype "input"))
      (node (ref "X1") (pin "1") (pinfunction "1_1") (pintype "passive"))
    )
    (net (code "23") (name "/RT_XTALO") (class "Default")
      (node (ref "C317") (pin "1") (pintype "passive"))
      (node (ref "R189") (pin "1") (pintype "passive"))
      (node (ref "U5") (pin "T16") (pinfunction "XTALO_T16") (pintype "output"))
      (node (ref "X1") (pin "3") (pinfunction "3_3") (pintype "passive"))
    )
    (net (code "24") (name "/USER_BUTTON") (class "Default")
      (node (ref "U5") (pin "R10") (pinfunction "GPIO_SNVS_00_R10") (pintype "bidirectional"))
    )
    (net (code "25") (name "/USER_LED") (class "Default")
      (node (ref "U5") (pin "M10") (pinfunction "GPIO_SNVS_03_M10") (pintype "bidirectional"))
    )
    (net (code "26") (name "/VDDA_ADC_3P3") (class "Default")
      (node (ref "C245") (pin "1") (pintype "passive"))
      (node (ref "C257") (pin "1") (pintype "passive"))
      (node (ref "FB1") (pin "1") (pinfunction "1_1") (pintype "passive"))
      (node (ref "U5") (pin "J13") (pinfunction "VDDA_ADC_3P3_J13") (pintype "power_in"))
    )
    (net (code "27") (name "/VDD_SNVS") (class "Default")
      (node (ref "C302") (pin "1") (pintype "passive"))
      (node (ref "R419") (pin "2") (pintype "passive"))
      (node (ref "TP11") (pin "1") (pintype "passive"))
      (node (ref "U5") (pin "U12") (pinfunction "VDD_SNVS_IN_U12") (pintype "power_in"))
    )
    (net (code "28") (name "/VSYS_SNVS_D") (class "Default")
      (node (ref "C21") (pin "1") (pintype "passive"))
      (node (ref "D2") (pin "A") (pinfunction "A_A") (pintype "passive"))
      (node (ref "U2") (pin "1") (pinfunction "VOUT_1") (pintype "power_in"))
    )
    (net (code "29") (name "/WAKEUP") (class "Default")
      (node (ref "TP9") (pin "1") (pintype "passive"))
      (node (ref "U5") (pin "T8") (pinfunction "WAKEUP_T8") (pintype "passive"))
    )
    (net (code "30") (name "/WIFI_POWER_EN") (class "Default")
      (node (ref "U5") (pin "R11") (pinfunction "GPIO_SNVS_09_R11") (pintype "bidirectional"))
    )
    (net (code "31") (name "ADC_1V8_IN") (class "Default")
      (node (ref "C117") (pin "1") (pintype "passive"))
      (node (ref "C136") (pin "1") (pintype "passive"))
      (node (ref "C347") (pin "1") (pintype "passive"))
      (node (ref "C348") (pin "1") (pintype "passive"))
      (node (ref "FB2") (pin "2") (pinfunction "2_2") (pintype "passive"))
      (node (ref "U5") (pin "G16") (pinfunction "ADC_VREFH_G16") (pintype "passive"))
      (node (ref "U5") (pin "K15") (pinfunction "VDDA_ADC_1P8_K15") (pintype "power_in"))
      (node (ref "U5") (pin "M11") (pinfunction "VDDA_1P8_IN_M11") (pintype "power_in"))
    )
    (net (code "32") (name "DCDC_1V8_OUT") (class "Default")
      (node (ref "C279") (pin "1") (pintype "passive"))
      (node (ref "FB2") (pin "1") (pinfunction "1_1") (pintype "passive"))
      (node (ref "R416") (pin "2") (pintype "passive"))
      (node (ref "U5") (pin "M6") (pinfunction "DCDC_ANA_SENSE_M6") (pintype "passive"))
    )
    (net (code "33") (name "DCDC_1V8_OUT_SENSE") (class "Default")
      (node (ref "C118") (pin "1") (pintype "passive"))
      (node (ref "C124") (pin "1") (pintype "passive"))
      (node (ref "C138") (pin "1") (pintype "passive"))
      (node (ref "C280") (pin "1") (pintype "passive"))
      (node (ref "R416") (pin "1") (pintype "passive"))
      (node (ref "U5") (pin "M7") (pinfunction "DCDC_ANA_1_M7") (pintype "passive"))
      (node (ref "U5") (pin "M8") (pinfunction "DCDC_ANA_2_M8") (pintype "passive"))
    )
    (net (code "34") (name "GND") (class "Default")
      (node (ref "C102") (pin "2") (pintype "passive"))
      (node (ref "C107") (pin "2") (pintype "passive"))
      (node (ref "C109") (pin "2") (pintype "passive"))
      (node (ref "C110") (pin "2") (pintype "passive"))
      (node (ref "C115") (pin "2") (pintype "passive"))
      (node (ref "C117") (pin "2") (pintype "passive"))
      (node (ref "C118") (pin "2") (pintype "passive"))
      (node (ref "C124") (pin "2") (pintype "passive"))
      (node (ref "C136") (pin "2") (pintype "passive"))
      (node (ref "C138") (pin "2") (pintype "passive"))
      (node (ref "C18") (pin "2") (pintype "passive"))
      (node (ref "C21") (pin "2") (pintype "passive"))
      (node (ref "C245") (pin "2") (pintype "passive"))
      (node (ref "C257") (pin "2") (pintype "passive"))
      (node (ref "C260") (pin "2") (pintype "passive"))
      (node (ref "C261") (pin "2") (pintype "passive"))
      (node (ref "C264") (pin "2") (pintype "passive"))
      (node (ref "C266") (pin "2") (pintype "passive"))
      (node (ref "C269") (pin "2") (pintype "passive"))
      (node (ref "C273") (pin "2") (pintype "passive"))
      (node (ref "C276") (pin "2") (pintype "passive"))
      (node (ref "C277") (pin "2") (pintype "passive"))
      (node (ref "C279") (pin "2") (pintype "passive"))
      (node (ref "C280") (pin "2") (pintype "passive"))
      (node (ref "C286") (pin "2") (pintype "passive"))
      (node (ref "C287") (pin "2") (pintype "passive"))
      (node (ref "C290") (pin "2") (pintype "passive"))
      (node (ref "C293") (pin "2") (pintype "passive"))
      (node (ref "C294") (pin "2") (pintype "passive"))
      (node (ref "C296") (pin "2") (pintype "passive"))
      (node (ref "C300") (pin "2") (pintype "passive"))
      (node (ref "C302") (pin "2") (pintype "passive"))
      (node (ref "C305") (pin "2") (pintype "passive"))
      (node (ref "C316") (pin "1") (pintype "passive"))
      (node (ref "C317") (pin "2") (pintype "passive"))
      (node (ref "C347") (pin "2") (pintype "passive"))
      (node (ref "C348") (pin "2") (pintype "passive"))
      (node (ref "C57") (pin "2") (pintype "passive"))
      (node (ref "C61") (pin "2") (pintype "passive"))
      (node (ref "C62") (pin "2") (pintype "passive"))
      (node (ref "C63") (pin "2") (pintype "passive"))
      (node (ref "C67") (pin "2") (pintype "passive"))
      (node (ref "C74") (pin "2") (pintype "passive"))
      (node (ref "D31") (pin "A") (pinfunction "A_A") (pintype "passive"))
      (node (ref "R14") (pin "2") (pintype "passive"))
      (node (ref "R398") (pin "1") (pintype "passive"))
      (node (ref "U2") (pin "2") (pinfunction "GND_2") (pintype "power_in"))
      (node (ref "U2") (pin "5") (pinfunction "TP-GND_5") (pintype "power_in"))
      (node (ref "U5") (pin "A1") (pinfunction "VSS_1_A1") (pintype "power_in"))
      (node (ref "U5") (pin "A17") (pinfunction "VSS_2_A17") (pintype "power_in"))
      (node (ref "U5") (pin "B7") (pinfunction "VSS_3_B7") (pintype "power_in"))
      (node (ref "U5") (pin "C10") (pinfunction "VSS_5_C10") (pintype "power_in"))
      (node (ref "U5") (pin "C12") (pinfunction "VSS_6_C12") (pintype "power_in"))
      (node (ref "U5") (pin "C14") (pinfunction "VSS_7_C14") (pintype "power_in"))
      (node (ref "U5") (pin "C8") (pinfunction "VSS_4_C8") (pintype "power_in"))
      (node (ref "U5") (pin "D4") (pinfunction "VSS_8_D4") (pintype "power_in"))
      (node (ref "U5") (pin "F11") (pinfunction "VSS_9_F11") (pintype "power_in"))
      (node (ref "U5") (pin "F12") (pinfunction "VSS_10_F12") (pintype "power_in"))
      (node (ref "U5") (pin "F13") (pinfunction "VSS_11_F13") (pintype "power_in"))
      (node (ref "U5") (pin "G10") (pinfunction "VSS_16_G10") (pintype "power_in"))
      (node (ref "U5") (pin "G11") (pinfunction "VSS_17_G11") (pintype "power_in"))
      (node (ref "U5") (pin "G15") (pinfunction "VSS_18_G15") (pintype "power_in"))
      (node (ref "U5") (pin "G3") (pinfunction "VSS_12_G3") (pintype "power_in"))
      (node (ref "U5") (pin "G7") (pinfunction "VSS_13_G7") (pintype "power_in"))
      (node (ref "U5") (pin "G8") (pinfunction "VSS_14_G8") (pintype "power_in"))
      (node (ref "U5") (pin "G9") (pinfunction "VSS_15_G9") (pintype "power_in"))
      (node (ref "U5") (pin "H11") (pinfunction "VSS_20_H11") (pintype "power_in"))
      (node (ref "U5") (pin "H7") (pinfunction "VSS_19_H7") (pintype "power_in"))
      (node (ref "U5") (pin "J11") (pinfunction "VSS_22_J11") (pintype "power_in"))
      (node (ref "U5") (pin "J7") (pinfunction "VSS_21_J7") (pintype "power_in"))
      (node (ref "U5") (pin "K11") (pinfunction "VSS_23_K11") (pintype "power_in"))
      (node (ref "U5") (pin "K6") (pinfunction "DCDC_GND_1_K6") (pintype "power_in"))
      (node (ref "U5") (pin "K7") (pinfunction "DCDC_GND_2_K7") (pintype "power_in"))
      (node (ref "U5") (pin "L10") (pinfunction "VSS_25_L10") (pintype "power_in"))
      (node (ref "U5") (pin "L11") (pinfunction "VSS_26_L11") (pintype "power_in"))
      (node (ref "U5") (pin "L15") (pinfunction "VSS_27_L15") (pintype "power_in"))
      (node (ref "U5") (pin "L3") (pinfunction "VSS_24_L3") (pintype "power_in"))
      (node (ref "U5") (pin "L6") (pinfunction "DCDC_GND_3_L6") (pintype "power_in"))
      (node (ref "U5") (pin "P14") (pinfunction "VSS_29_P14") (pintype "power_in"))
      (node (ref "U5") (pin "P4") (pinfunction "VSS_28_P4") (pintype "power_in"))
      (node (ref "U5") (pin "R4") (pinfunction "VSS_34_R4") (pintype "power_in"))
      (node (ref "U5") (pin "R7") (pinfunction "VSS_30_R7") (pintype "power_in"))
      (node (ref "U5") (pin "T12") (pinfunction "VSS_31_T12") (pintype "power_in"))
      (node (ref "U5") (pin "U1") (pinfunction "VSS_32_U1") (pintype "power_in"))
      (node (ref "U5") (pin "U17") (pinfunction "VSS_33_U17") (pintype "power_in"))
      (node (ref "X1") (pin "2") (pinfunction "GND_2") (pintype "power_in"))
      (node (ref "X1") (pin "4") (pinfunction "GND_4") (pintype "power_in"))
    )
    (net (code "35") (name "MCU_DCDC_IN") (class "Default")
      (node (ref "C102") (pin "1") (pintype "passive"))
      (node (ref "C277") (pin "1") (pintype "passive"))
      (node (ref "C294") (pin "1") (pintype "passive"))
      (node (ref "R194") (pin "2") (pintype "passive"))
      (node (ref "R396") (pin "1") (pintype "passive"))
      (node (ref "R397") (pin "1") (pintype "passive"))
      (node (ref "TP17") (pin "1") (pintype "passive"))
      (node (ref "U5") (pin "L5") (pinfunction "DCDC_IN_Q_L5") (pintype "passive"))
      (node (ref "U5") (pin "M5") (pinfunction "DCDC_IN_1_M5") (pintype "passive"))
      (node (ref "U5") (pin "N5") (pinfunction "DCDC_IN_2_N5") (pintype "passive"))
    )
    (net (code "36") (name "Net-(U5C-DCDC_DIG_1)") (class "Default")
      (node (ref "C269") (pin "1") (pintype "passive"))
      (node (ref "C57") (pin "1") (pintype "passive"))
      (node (ref "C63") (pin "1") (pintype "passive"))
      (node (ref "C74") (pin "1") (pintype "passive"))
      (node (ref "R117") (pin "1") (pintype "passive"))
      (node (ref "U5") (pin "K8") (pinfunction "DCDC_DIG_1_K8") (pintype "passive"))
      (node (ref "U5") (pin "K9") (pinfunction "DCDC_DIG_2_K9") (pintype "passive"))
      (node (ref "U5") (pin "L8") (pinfunction "DCDC_DIG_3_L8") (pintype "passive"))
    )
    (net (code "37") (name "VDDA_1P0") (class "Default")
      (node (ref "C276") (pin "1") (pintype "passive"))
      (node (ref "U5") (pin "N11") (pinfunction "VDDA_1P0_N11") (pintype "power_in"))
    )
    (net (code "38") (name "VDD_3V3") (class "Default")
      (node (ref "FB1") (pin "2") (pinfunction "2_2") (pintype "passive"))
      (node (ref "R194") (pin "1") (pintype "passive"))
      (node (ref "R415") (pin "1") (pintype "passive"))
      (node (ref "TP14") (pin "1") (pintype "passive"))
      (node (ref "TP16") (pin "1") (pintype "passive"))
    )
    (net (code "39") (name "VDD_COIN_3V") (class "Default")
      (node (ref "D3") (pin "A") (pinfunction "A_A") (pintype "passive"))
    )
    (net (code "40") (name "VDD_LPSR_ANA") (class "Default")
      (node (ref "C290") (pin "1") (pintype "passive"))
      (node (ref "U5") (pin "P12") (pinfunction "VDD_LPSR_ANA_P12") (pintype "power_in"))
    )
    (net (code "41") (name "VDD_LPSR_DIG") (class "Default")
      (node (ref "C296") (pin "1") (pintype "passive"))
      (node (ref "U5") (pin "P11") (pinfunction "VDD_LPSR_DIG_P11") (pintype "power_in"))
    )
    (net (code "42") (name "VDD_LPSR_IN") (class "Default")
      (node (ref "C300") (pin "1") (pintype "passive"))
      (node (ref "R415") (pin "2") (pintype "passive"))
      (node (ref "TP15") (pin "1") (pintype "passive"))
      (node (ref "U5") (pin "R12") (pinfunction "VDD_LPSR_IN_R12") (pintype "power_in"))
    )
    (net (code "43") (name "VDD_SNVS_3V3") (class "Default")
      (node (ref "D2") (pin "K") (pinfunction "K_K") (pintype "passive"))
      (node (ref "D3") (pin "K") (pinfunction "K_K") (pintype "passive"))
      (node (ref "R419") (pin "1") (pintype "passive"))
      (node (ref "TP10") (pin "1") (pintype "passive"))
    )
    (net (code "44") (name "VDD_SNVS_ANA") (class "Default")
      (node (ref "C293") (pin "1") (pintype "passive"))
      (node (ref "C305") (pin "1") (pintype "passive"))
      (node (ref "R1821") (pin "2") (pintype "passive"))
      (node (ref "R215") (pin "2") (pintype "passive"))
      (node (ref "U5") (pin "U11") (pinfunction "NVCC_SNVS_U11") (pintype "passive"))
      (node (ref "U5") (pin "U14") (pinfunction "VDD_SNVS_ANA_U14") (pintype "power_in"))
    )
    (net (code "45") (name "VDD_SNVS_DIG") (class "Default")
      (node (ref "C107") (pin "1") (pintype "passive"))
      (node (ref "U5") (pin "T14") (pinfunction "VDD_SNVS_DIG_T14") (pintype "power_in"))
    )
    (net (code "46") (name "VDD_SOC_IN") (class "Default")
      (node (ref "C260") (pin "1") (pintype "passive"))
      (node (ref "C261") (pin "1") (pintype "passive"))
      (node (ref "C264") (pin "1") (pintype "passive"))
      (node (ref "C266") (pin "1") (pintype "passive"))
      (node (ref "C273") (pin "1") (pintype "passive"))
      (node (ref "C61") (pin "1") (pintype "passive"))
      (node (ref "C62") (pin "1") (pintype "passive"))
      (node (ref "C67") (pin "1") (pintype "passive"))
      (node (ref "R117") (pin "2") (pintype "passive"))
      (node (ref "U5") (pin "H10") (pinfunction "VDD_SOC_IN_3_H10") (pintype "passive"))
      (node (ref "U5") (pin "H8") (pinfunction "VDD_SOC_IN_1_H8") (pintype "passive"))
      (node (ref "U5") (pin "H9") (pinfunction "VDD_SOC_IN_2_H9") (pintype "passive"))
      (node (ref "U5") (pin "J10") (pinfunction "VDD_SOC_IN_6_J10") (pintype "passive"))
      (node (ref "U5") (pin "J8") (pinfunction "VDD_SOC_IN_4_J8") (pintype "passive"))
      (node (ref "U5") (pin "J9") (pinfunction "VDD_SOC_IN_5_J9") (pintype "passive"))
      (node (ref "U5") (pin "K10") (pinfunction "VDD_SOC_IN_7_K10") (pintype "passive"))
      (node (ref "U5") (pin "L7") (pinfunction "DCDC_DIG_SENSE_L7") (pintype "passive"))
    )
    (net (code "47") (name "VSYS") (class "Default")
      (node (ref "C18") (pin "1") (pintype "passive"))
      (node (ref "U2") (pin "3") (pinfunction "CONTROL_3") (pintype "passive"))
      (node (ref "U2") (pin "4") (pinfunction "VIN_4") (pintype "power_in"))
    )
  )
)
